# stc15.net
KiCad netlist of a schematic drawn in Altium Designer
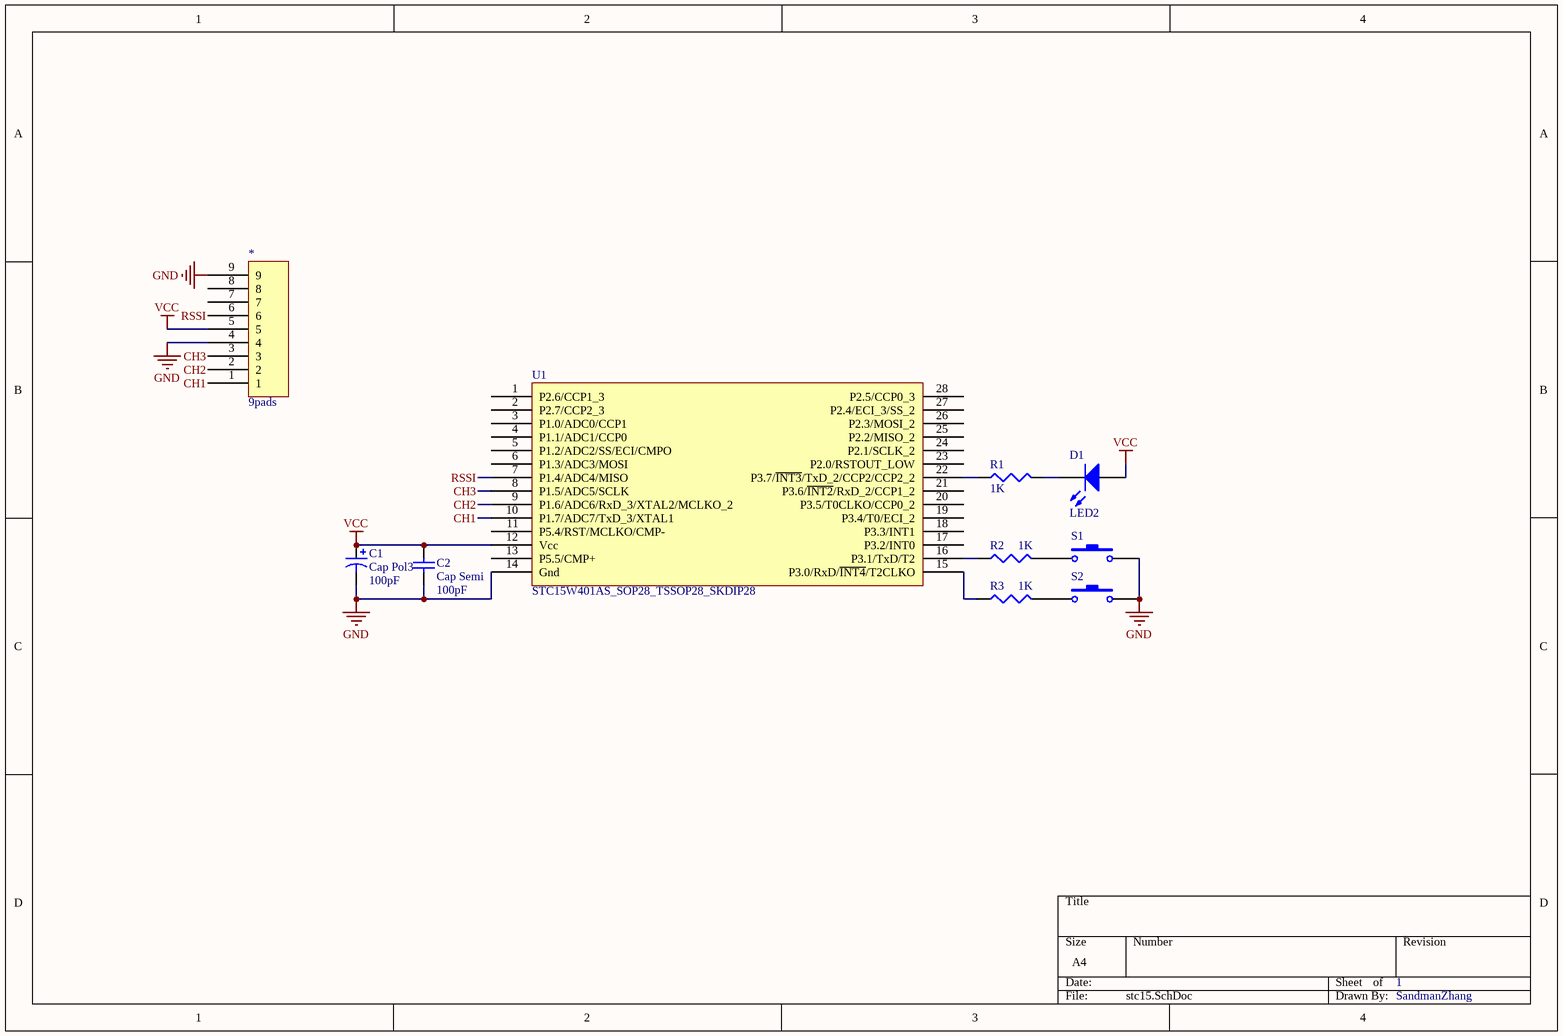
[diagram p0: stc15.SchDoc]

(export (version "E")
  (design (tool "Eeschema 10.0.6"))
  (components
    (comp (ref "*") (value "9pads") (footprint "9pads") (libsource (lib "Connectivity_pads") (part "9pads")))
    (comp (ref "C1")
      (value "Cap Pol3")
      (footprint "C0805")
      (description "Polarized Capacitor (Surface Mount)")
      (fields (field (name "ALTIUM_VALUE") "100pF") (field (name "PUBLISHER") "Altium Limited"))
      (libsource (lib "Miscellaneous Devices") (part "Cap Pol3"))
    )
    (comp (ref "C2")
      (value "Cap Semi")
      (footprint "1608[0603]")
      (description "Capacitor (Semiconductor SIM Model)")
      (fields (field (name "ALTIUM_VALUE") "100pF") (field (name "PUBLISHER") "Altium Limited"))
      (libsource (lib "Miscellaneous Devices") (part "Cap Semi"))
    )
    (comp (ref "D1")
      (value "LED2")
      (footprint "Miscellaneous Devices:6-0805_N")
      (description "Typical RED, GREEN, YELLOW, AMBER GaAs LED")
      (fields (field (name "PUBLISHER") "Altium Limited"))
      (libsource (lib "Miscellaneous Devices") (part "LED2"))
    )
    (comp (ref "R1")
      (value "1K")
      (footprint "J1-0603")
      (description "Resistor")
      (fields (field (name "Comment") "Res3") (field (name "PUBLISHER") "Altium Limited"))
      (libsource (lib "Miscellaneous Devices") (part "Res3"))
    )
    (comp (ref "R2")
      (value "1K")
      (footprint "J1-0603")
      (description "Resistor")
      (fields (field (name "Comment") "Res3") (field (name "PUBLISHER") "Altium Limited"))
      (libsource (lib "Miscellaneous Devices") (part "Res3"))
    )
    (comp (ref "R3")
      (value "1K")
      (footprint "J1-0603")
      (description "Resistor")
      (fields (field (name "Comment") "Res3") (field (name "PUBLISHER") "Altium Limited"))
      (libsource (lib "Miscellaneous Devices") (part "Res3"))
    )
    (comp (ref "S1")
      (value "SW-PB")
      (footprint "SPST-2")
      (description "Switch")
      (fields (field (name "PUBLISHER") "Altium Limited"))
      (libsource (lib "Miscellaneous Devices") (part "SW-PB"))
    )
    (comp (ref "S2")
      (value "SW-PB")
      (footprint "SPST-2")
      (description "Switch")
      (fields (field (name "PUBLISHER") "Altium Limited"))
      (libsource (lib "Miscellaneous Devices") (part "SW-PB"))
    )
    (comp (ref "U1")
      (value "STC15W401AS_SOP28_TSSOP28_SKDIP28")
      (footprint "SOP28")
      (libsource (lib "stcmcu_altium20.1.10") (part "STC15W401AS_SOP28_TSSOP28_SKDIP28"))
    )
  )
  (nets
    (net (code "1") (name "/CH1") (class "Default")
      (node (ref "*") (pin "1") (pinfunction "1_1") (pintype "passive"))
      (node (ref "U1") (pin "10") (pinfunction "P1.7/ADC7/TxD_3/XTAL1_10") (pintype "passive"))
    )
    (net (code "2") (name "/CH2") (class "Default")
      (node (ref "*") (pin "2") (pinfunction "2_2") (pintype "passive"))
      (node (ref "U1") (pin "9") (pinfunction "P1.6/ADC6/RxD_3/XTAL2/MCLKO_2_9") (pintype "passive"))
    )
    (net (code "3") (name "/CH3") (class "Default")
      (node (ref "*") (pin "3") (pinfunction "3_3") (pintype "passive"))
      (node (ref "U1") (pin "8") (pinfunction "P1.5/ADC5/SCLK_8") (pintype "passive"))
    )
    (net (code "4") (name "/RSSI") (class "Default")
      (node (ref "*") (pin "6") (pinfunction "6_6") (pintype "passive"))
      (node (ref "U1") (pin "7") (pinfunction "P1.4/ADC4/MISO_7") (pintype "passive"))
    )
    (net (code "5") (name "GND") (class "Default")
      (node (ref "*") (pin "4") (pinfunction "4_4") (pintype "passive"))
      (node (ref "*") (pin "9") (pinfunction "9_9") (pintype "passive"))
      (node (ref "C1") (pin "2") (pinfunction "2_2") (pintype "passive"))
      (node (ref "C2") (pin "1") (pinfunction "1_1") (pintype "passive"))
      (node (ref "S1") (pin "2") (pinfunction "2_2") (pintype "passive"))
      (node (ref "S2") (pin "2") (pinfunction "2_2") (pintype "passive"))
      (node (ref "U1") (pin "14") (pinfunction "Gnd_14") (pintype "passive"))
    )
    (net (code "6") (name "Net-(D1-K)") (class "Default")
      (node (ref "D1") (pin "2") (pinfunction "K_2") (pintype "passive"))
      (node (ref "R1") (pin "2") (pinfunction "2_2") (pintype "passive"))
    )
    (net (code "7") (name "Net-(R2-Pad2)") (class "Default")
      (node (ref "R2") (pin "2") (pinfunction "2_2") (pintype "passive"))
      (node (ref "S1") (pin "1") (pinfunction "1_1") (pintype "passive"))
    )
    (net (code "8") (name "Net-(R3-Pad2)") (class "Default")
      (node (ref "R3") (pin "2") (pinfunction "2_2") (pintype "passive"))
      (node (ref "S2") (pin "1") (pinfunction "1_1") (pintype "passive"))
    )
    (net (code "9") (name "Net-(U1-P3.0{slash}RxD{slash}~{INT4}{slash}T2CLKO)") (class "Default")
      (node (ref "R3") (pin "1") (pinfunction "1_1") (pintype "passive"))
      (node (ref "U1") (pin "15") (pinfunction "P3.0/RxD/~{INT4}/T2CLKO_15") (pintype "passive"))
    )
    (net (code "10") (name "Net-(U1-P3.1{slash}TxD{slash}T2)") (class "Default")
      (node (ref "R2") (pin "1") (pinfunction "1_1") (pintype "passive"))
      (node (ref "U1") (pin "16") (pinfunction "P3.1/TxD/T2_16") (pintype "passive"))
    )
    (net (code "11") (name "Net-(U1-P3.7{slash}~{INT3}{slash}TxD_2{slash}CCP2{slash}CCP2_2)") (class "Default")
      (node (ref "R1") (pin "1") (pinfunction "1_1") (pintype "passive"))
      (node (ref "U1") (pin "22") (pinfunction "P3.7/~{INT3}/TxD_2/CCP2/CCP2_2_22") (pintype "passive"))
    )
    (net (code "12") (name "VCC") (class "Default")
      (node (ref "*") (pin "5") (pinfunction "5_5") (pintype "passive"))
      (node (ref "C1") (pin "1") (pinfunction "1_1") (pintype "passive"))
      (node (ref "C2") (pin "2") (pinfunction "2_2") (pintype "passive"))
      (node (ref "D1") (pin "1") (pinfunction "A_1") (pintype "passive"))
      (node (ref "U1") (pin "12") (pinfunction "Vcc_12") (pintype "passive"))
    )
    (net (code "13") (name "unconnected-(*-Pad7)") (class "Default")
      (node (ref "*") (pin "7") (pinfunction "7_7") (pintype "passive"))
    )
    (net (code "14") (name "unconnected-(*-Pad8)") (class "Default")
      (node (ref "*") (pin "8") (pinfunction "8_8") (pintype "passive"))
    )
    (net (code "15") (name "unconnected-(U1-P1.0{slash}ADC0{slash}CCP1-Pad3)") (class "Default")
      (node (ref "U1") (pin "3") (pinfunction "P1.0/ADC0/CCP1_3") (pintype "passive"))
    )
    (net (code "16") (name "unconnected-(U1-P1.1{slash}ADC1{slash}CCP0-Pad4)") (class "Default")
      (node (ref "U1") (pin "4") (pinfunction "P1.1/ADC1/CCP0_4") (pintype "passive"))
    )
    (net (code "17") (name "unconnected-(U1-P1.2{slash}ADC2{slash}SS{slash}ECI{slash}CMPO-Pad5)") (class "Default")
      (node (ref "U1") (pin "5") (pinfunction "P1.2/ADC2/SS/ECI/CMPO_5") (pintype "passive"))
    )
    (net (code "18") (name "unconnected-(U1-P1.3{slash}ADC3{slash}MOSI-Pad6)") (class "Default")
      (node (ref "U1") (pin "6") (pinfunction "P1.3/ADC3/MOSI_6") (pintype "passive"))
    )
    (net (code "19") (name "unconnected-(U1-P2.0{slash}RSTOUT_LOW-Pad23)") (class "Default")
      (node (ref "U1") (pin "23") (pinfunction "P2.0/RSTOUT_LOW_23") (pintype "passive"))
    )
    (net (code "20") (name "unconnected-(U1-P2.1{slash}SCLK_2-Pad24)") (class "Default")
      (node (ref "U1") (pin "24") (pinfunction "P2.1/SCLK_2_24") (pintype "passive"))
    )
    (net (code "21") (name "unconnected-(U1-P2.2{slash}MISO_2-Pad25)") (class "Default")
      (node (ref "U1") (pin "25") (pinfunction "P2.2/MISO_2_25") (pintype "passive"))
    )
    (net (code "22") (name "unconnected-(U1-P2.3{slash}MOSI_2-Pad26)") (class "Default")
      (node (ref "U1") (pin "26") (pinfunction "P2.3/MOSI_2_26") (pintype "passive"))
    )
    (net (code "23") (name "unconnected-(U1-P2.4{slash}ECI_3{slash}SS_2-Pad27)") (class "Default")
      (node (ref "U1") (pin "27") (pinfunction "P2.4/ECI_3/SS_2_27") (pintype "passive"))
    )
    (net (code "24") (name "unconnected-(U1-P2.5{slash}CCP0_3-Pad28)") (class "Default")
      (node (ref "U1") (pin "28") (pinfunction "P2.5/CCP0_3_28") (pintype "passive"))
    )
    (net (code "25") (name "unconnected-(U1-P2.6{slash}CCP1_3-Pad1)") (class "Default")
      (node (ref "U1") (pin "1") (pinfunction "P2.6/CCP1_3_1") (pintype "passive"))
    )
    (net (code "26") (name "unconnected-(U1-P2.7{slash}CCP2_3-Pad2)") (class "Default")
      (node (ref "U1") (pin "2") (pinfunction "P2.7/CCP2_3_2") (pintype "passive"))
    )
    (net (code "27") (name "unconnected-(U1-P3.2{slash}INT0-Pad17)") (class "Default")
      (node (ref "U1") (pin "17") (pinfunction "P3.2/INT0_17") (pintype "passive"))
    )
    (net (code "28") (name "unconnected-(U1-P3.3{slash}INT1-Pad18)") (class "Default")
      (node (ref "U1") (pin "18") (pinfunction "P3.3/INT1_18") (pintype "passive"))
    )
    (net (code "29") (name "unconnected-(U1-P3.4{slash}T0{slash}ECI_2-Pad19)") (class "Default")
      (node (ref "U1") (pin "19") (pinfunction "P3.4/T0/ECI_2_19") (pintype "passive"))
    )
    (net (code "30") (name "unconnected-(U1-P3.5{slash}T0CLKO{slash}CCP0_2-Pad20)") (class "Default")
      (node (ref "U1") (pin "20") (pinfunction "P3.5/T0CLKO/CCP0_2_20") (pintype "passive"))
    )
    (net (code "31") (name "unconnected-(U1-P3.6{slash}~{INT2}{slash}RxD_2{slash}CCP1_2-Pad21)") (class "Default")
      (node (ref "U1") (pin "21") (pinfunction "P3.6/~{INT2}/RxD_2/CCP1_2_21") (pintype "passive"))
    )
    (net (code "32") (name "unconnected-(U1-P5.4{slash}RST{slash}MCLKO{slash}CMP--Pad11)") (class "Default")
      (node (ref "U1") (pin "11") (pinfunction "P5.4/RST/MCLKO/CMP-_11") (pintype "passive"))
    )
    (net (code "33") (name "unconnected-(U1-P5.5{slash}CMP+-Pad13)") (class "Default")
      (node (ref "U1") (pin "13") (pinfunction "P5.5/CMP+_13") (pintype "passive"))
    )
  )
)
